# MCU_GPIO.net
KiCad netlist of a schematic drawn in Altium Designer
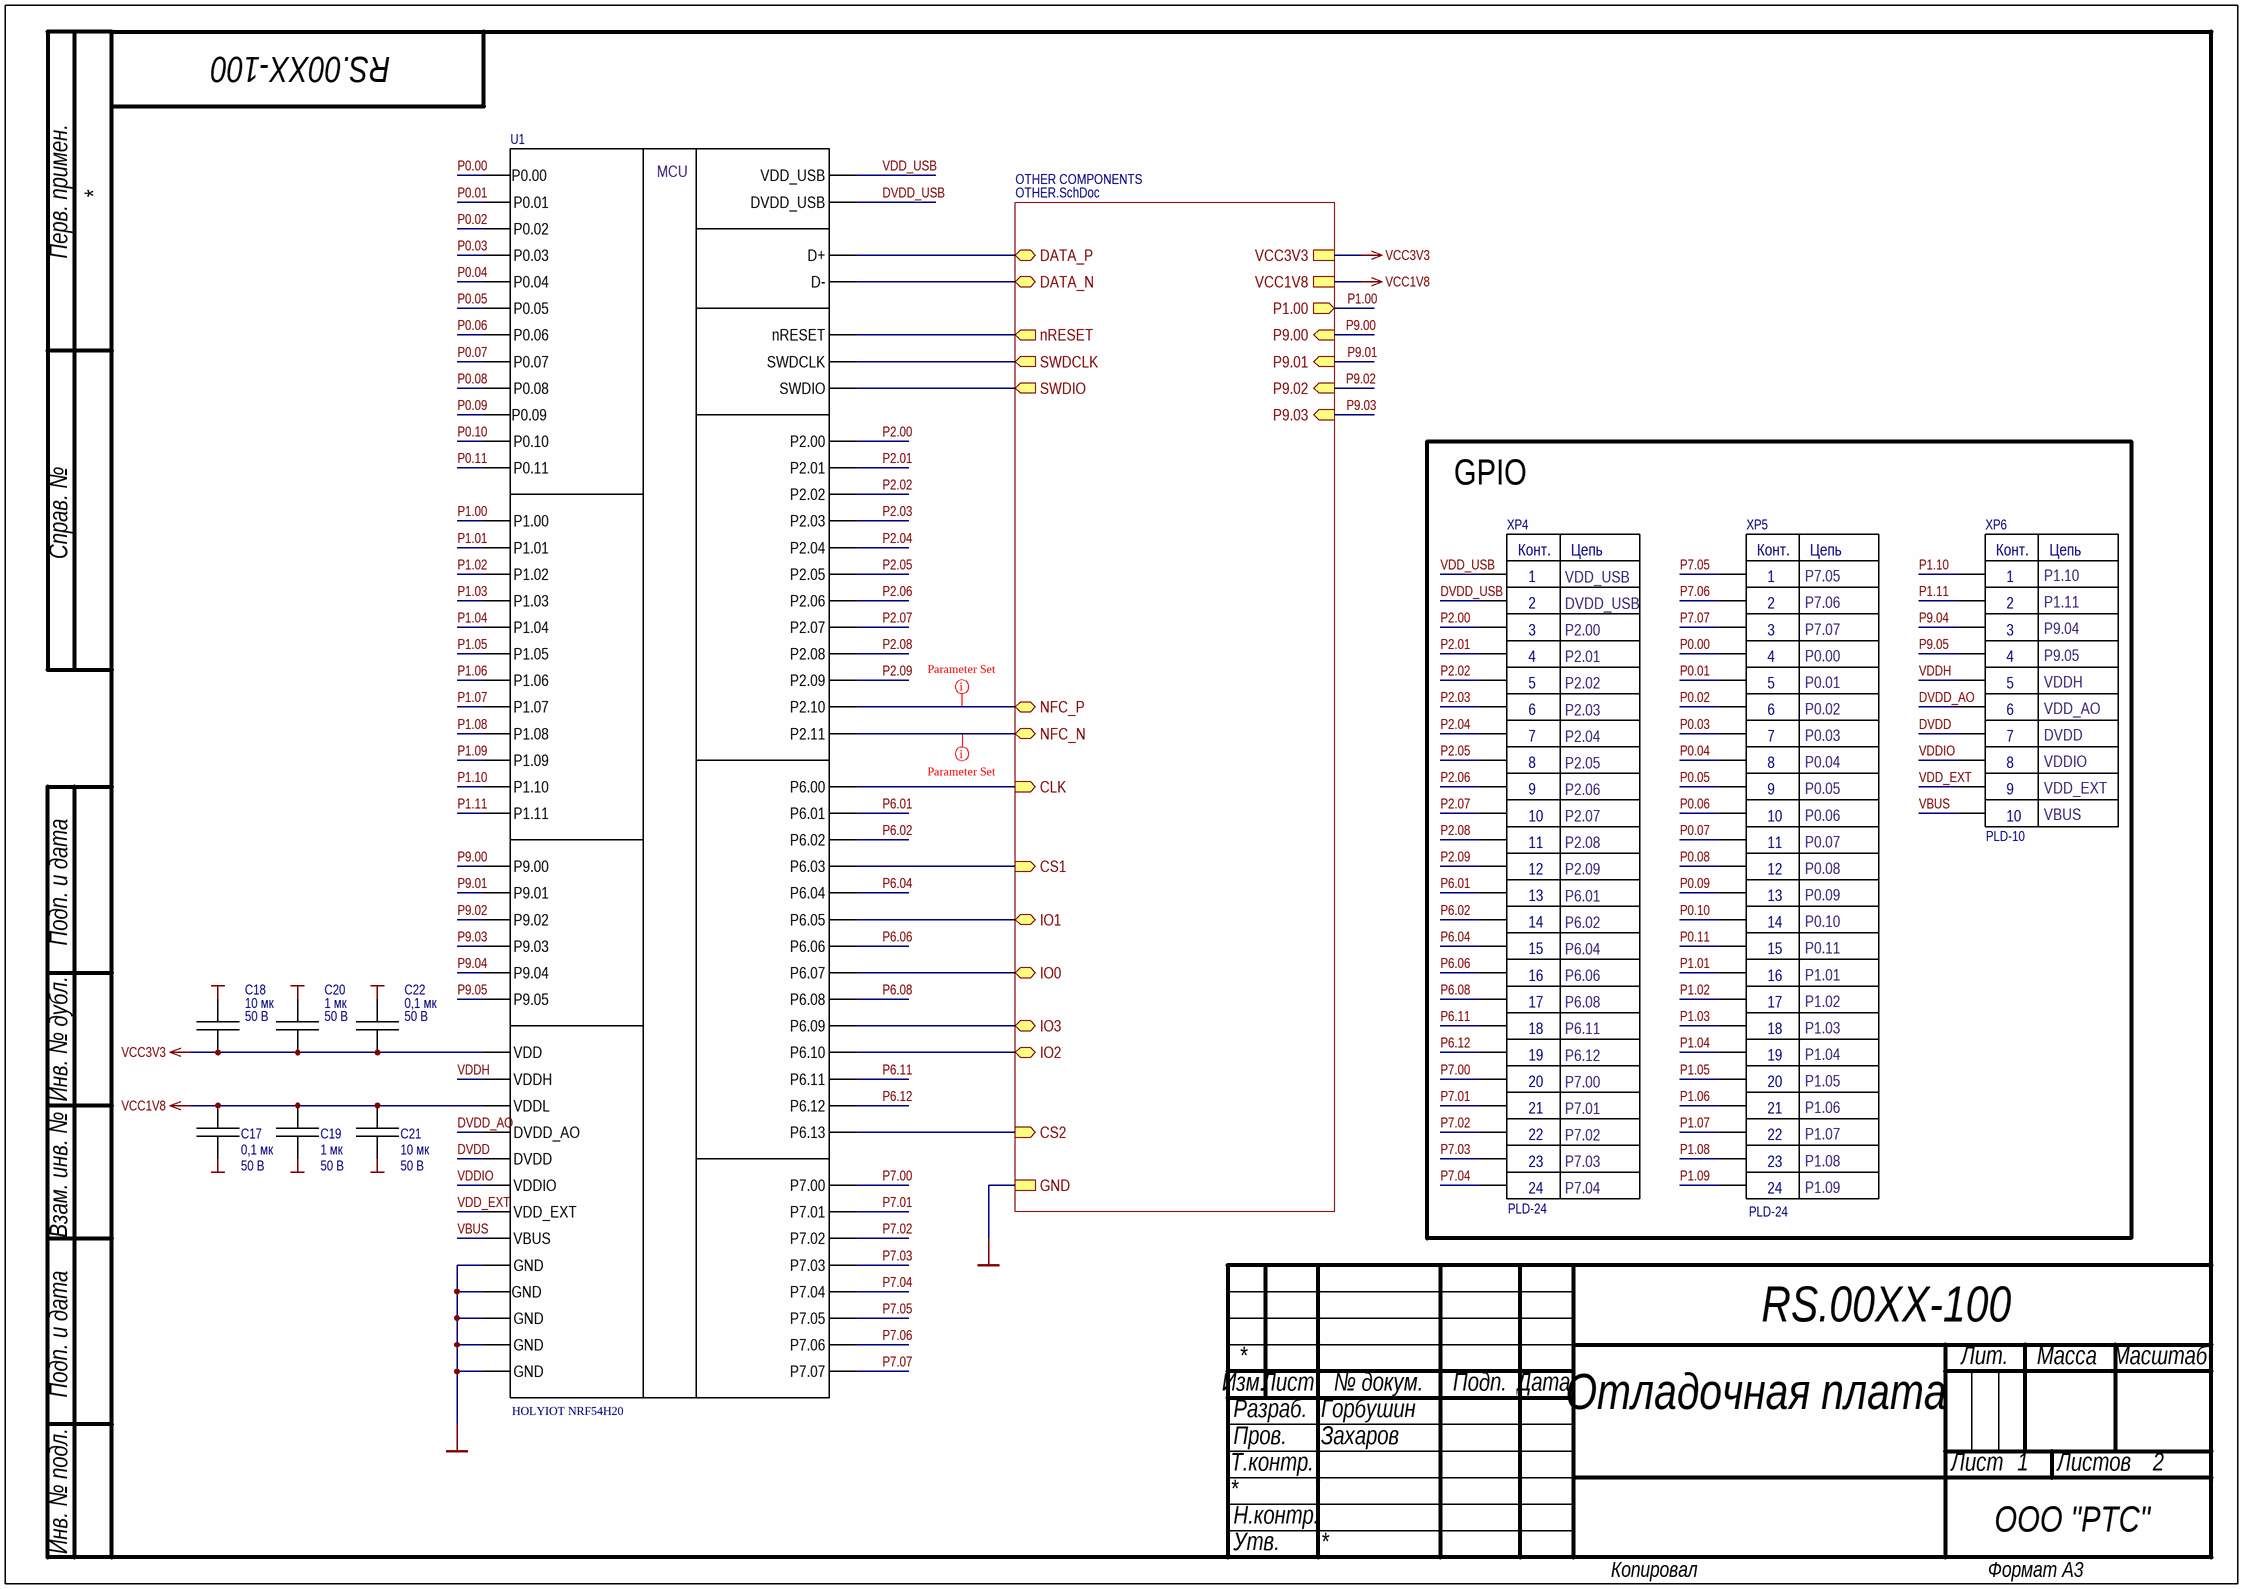
[diagram p0: MCU+GPIO.SchDoc]

(export (version "E")
  (design (tool "Eeschema 10.0.6"))
  (components
    (comp (ref "C17")
      (value "0,1 мк")
      (footprint "C_0603_Manual_mount")
      (description "Chip Monolithic Ceramic Capacitor")
      (fields
        (field (name "TOLERANCE") "10 %")
        (field (name "MANUFACTURER") "Murata Manufacturing")
        (field (name "RATED VOLTAGE") "50 В")
      )
      (libsource (lib "passive") (part "Capacitor"))
    )
    (comp (ref "C18")
      (value "10 мк")
      (footprint "C_1210_Manual_mount")
      (description "Chip Monolithic Ceramic Capacitor")
      (fields
        (field (name "TOLERANCE") "20 %")
        (field (name "MANUFACTURER") "Murata Manufacturing")
        (field (name "RATED VOLTAGE") "50 В")
      )
      (libsource (lib "passive") (part "Capacitor"))
    )
    (comp (ref "C19")
      (value "1 мк")
      (footprint "C_1206_Manual_mount")
      (description "Chip Monolithic Ceramic Capacitor")
      (fields
        (field (name "TOLERANCE") "10 %")
        (field (name "MANUFACTURER") "Murata Manufacturing")
        (field (name "RATED VOLTAGE") "50 В")
      )
      (libsource (lib "passive") (part "Capacitor"))
    )
    (comp (ref "C20")
      (value "1 мк")
      (footprint "C_1206_Manual_mount")
      (description "Chip Monolithic Ceramic Capacitor")
      (fields
        (field (name "TOLERANCE") "10 %")
        (field (name "MANUFACTURER") "Murata Manufacturing")
        (field (name "RATED VOLTAGE") "50 В")
      )
      (libsource (lib "passive") (part "Capacitor"))
    )
    (comp (ref "C21")
      (value "10 мк")
      (footprint "C_1210_Manual_mount")
      (description "Chip Monolithic Ceramic Capacitor")
      (fields
        (field (name "TOLERANCE") "20 %")
        (field (name "MANUFACTURER") "Murata Manufacturing")
        (field (name "RATED VOLTAGE") "50 В")
      )
      (libsource (lib "passive") (part "Capacitor"))
    )
    (comp (ref "C22")
      (value "0,1 мк")
      (footprint "C_0603_Manual_mount")
      (description "Chip Monolithic Ceramic Capacitor")
      (fields
        (field (name "TOLERANCE") "10 %")
        (field (name "MANUFACTURER") "Murata Manufacturing")
        (field (name "RATED VOLTAGE") "50 В")
      )
      (libsource (lib "passive") (part "Capacitor"))
    )
    (comp (ref "U1")
      (value "HOLYIOT NRF54H20")
      (footprint "HOLYIOT NRF54H20")
      (libsource (lib "Schlib1") (part "HOLYIOT NRF54H20"))
    )
    (comp (ref "XP4")
      (value "PLD-24")
      (footprint "PLD-24")
      (description "PLD connector")
      (fields (field (name "MANUFACTURER") "NONAME"))
      (libsource (lib "altium-lib") (part "PLD-24"))
    )
    (comp (ref "XP5")
      (value "PLD-24")
      (footprint "PLD-24")
      (description "PLD connector")
      (fields (field (name "MANUFACTURER") "NONAME"))
      (libsource (lib "altium-lib") (part "PLD-24"))
    )
    (comp (ref "XP6")
      (value "PLD-10")
      (footprint "PLD-10")
      (description "PLD connector")
      (fields (field (name "MANUFACTURER") "NONAME"))
      (libsource (lib "altium-lib") (part "PLD-10"))
    )
  )
  (nets
    (net (code "1") (name "/CLK") (class "Default")
      (node (ref "U1") (pin "15") (pinfunction "P6.00_15") (pintype "passive"))
    )
    (net (code "2") (name "/CS1") (class "Default")
      (node (ref "U1") (pin "18") (pinfunction "P6.03_18") (pintype "passive"))
    )
    (net (code "3") (name "/CS2") (class "Default")
      (node (ref "U1") (pin "7") (pinfunction "P6.13_7") (pintype "passive"))
    )
    (net (code "4") (name "/DATA_N") (class "Default")
      (node (ref "U1") (pin "78") (pinfunction "D-_78") (pintype "passive"))
    )
    (net (code "5") (name "/DATA_P") (class "Default")
      (node (ref "U1") (pin "79") (pinfunction "D+_79") (pintype "passive"))
    )
    (net (code "6") (name "/DVDD") (class "Default")
      (node (ref "U1") (pin "5") (pinfunction "DVDD_5") (pintype "passive"))
      (node (ref "XP6") (pin "7") (pinfunction "7_7") (pintype "passive"))
    )
    (net (code "7") (name "/DVDD_AO") (class "Default")
      (node (ref "U1") (pin "6") (pinfunction "DVDD_AO_6") (pintype "passive"))
      (node (ref "XP6") (pin "6") (pinfunction "6_6") (pintype "passive"))
    )
    (net (code "8") (name "/DVDD_USB") (class "Default")
      (node (ref "U1") (pin "76") (pinfunction "DVDD_USB_76") (pintype "passive"))
      (node (ref "XP4") (pin "2") (pinfunction "2_2") (pintype "passive"))
    )
    (net (code "9") (name "/IO0") (class "Default")
      (node (ref "U1") (pin "13") (pinfunction "P6.07_13") (pintype "passive"))
    )
    (net (code "10") (name "/IO1") (class "Default")
      (node (ref "U1") (pin "20") (pinfunction "P6.05_20") (pintype "passive"))
    )
    (net (code "11") (name "/IO2") (class "Default")
      (node (ref "U1") (pin "10") (pinfunction "P6.10_10") (pintype "passive"))
    )
    (net (code "12") (name "/IO3") (class "Default")
      (node (ref "U1") (pin "11") (pinfunction "P6.09_11") (pintype "passive"))
    )
    (net (code "13") (name "/NFC_N") (class "Default")
      (node (ref "U1") (pin "26") (pinfunction "P2.11_26") (pintype "passive"))
    )
    (net (code "14") (name "/NFC_P") (class "Default")
      (node (ref "U1") (pin "27") (pinfunction "P2.10_27") (pintype "passive"))
    )
    (net (code "15") (name "/P0.00") (class "Default")
      (node (ref "U1") (pin "50") (pinfunction "_P0.00_50") (pintype "passive"))
      (node (ref "XP5") (pin "4") (pinfunction "4_4") (pintype "passive"))
    )
    (net (code "16") (name "/P0.01") (class "Default")
      (node (ref "U1") (pin "68") (pinfunction "P0.01_68") (pintype "passive"))
      (node (ref "XP5") (pin "5") (pinfunction "5_5") (pintype "passive"))
    )
    (net (code "17") (name "/P0.02") (class "Default")
      (node (ref "U1") (pin "67") (pinfunction "P0.02_67") (pintype "passive"))
      (node (ref "XP5") (pin "6") (pinfunction "6_6") (pintype "passive"))
    )
    (net (code "18") (name "/P0.03") (class "Default")
      (node (ref "U1") (pin "66") (pinfunction "P0.03_66") (pintype "passive"))
      (node (ref "XP5") (pin "7") (pinfunction "7_7") (pintype "passive"))
    )
    (net (code "19") (name "/P0.04") (class "Default")
      (node (ref "U1") (pin "51") (pinfunction "P0.04_51") (pintype "passive"))
      (node (ref "XP5") (pin "8") (pinfunction "8_8") (pintype "passive"))
    )
    (net (code "20") (name "/P0.05") (class "Default")
      (node (ref "U1") (pin "45") (pinfunction "P0.05_45") (pintype "passive"))
      (node (ref "XP5") (pin "9") (pinfunction "9_9") (pintype "passive"))
    )
    (net (code "21") (name "/P0.06") (class "Default")
      (node (ref "U1") (pin "46") (pinfunction "P0.06_46") (pintype "passive"))
      (node (ref "XP5") (pin "10") (pinfunction "10_10") (pintype "passive"))
    )
    (net (code "22") (name "/P0.07") (class "Default")
      (node (ref "U1") (pin "47") (pinfunction "P0.07_47") (pintype "passive"))
      (node (ref "XP5") (pin "11") (pinfunction "11_11") (pintype "passive"))
    )
    (net (code "23") (name "/P0.08") (class "Default")
      (node (ref "U1") (pin "44") (pinfunction "P0.08_44") (pintype "passive"))
      (node (ref "XP5") (pin "12") (pinfunction "12_12") (pintype "passive"))
    )
    (net (code "24") (name "/P0.09") (class "Default")
      (node (ref "U1") (pin "43") (pinfunction "_P0.09_43") (pintype "passive"))
      (node (ref "XP5") (pin "13") (pinfunction "13_13") (pintype "passive"))
    )
    (net (code "25") (name "/P0.10") (class "Default")
      (node (ref "U1") (pin "69") (pinfunction "P0.10_69") (pintype "passive"))
      (node (ref "XP5") (pin "14") (pinfunction "14_14") (pintype "passive"))
    )
    (net (code "26") (name "/P0.11") (class "Default")
      (node (ref "U1") (pin "70") (pinfunction "P0.11_70") (pintype "passive"))
      (node (ref "XP5") (pin "15") (pinfunction "15_15") (pintype "passive"))
    )
    (net (code "27") (name "/P1.00") (class "Default")
      (node (ref "U1") (pin "57") (pinfunction "P1.00_57") (pintype "passive"))
    )
    (net (code "28") (name "/P1.01") (class "Default")
      (node (ref "U1") (pin "56") (pinfunction "P1.01_56") (pintype "passive"))
      (node (ref "XP5") (pin "16") (pinfunction "16_16") (pintype "passive"))
    )
    (net (code "29") (name "/P1.02") (class "Default")
      (node (ref "U1") (pin "54") (pinfunction "P1.02_54") (pintype "passive"))
      (node (ref "XP5") (pin "17") (pinfunction "17_17") (pintype "passive"))
    )
    (net (code "30") (name "/P1.03") (class "Default")
      (node (ref "U1") (pin "53") (pinfunction "P1.03_53") (pintype "passive"))
      (node (ref "XP5") (pin "18") (pinfunction "18_18") (pintype "passive"))
    )
    (net (code "31") (name "/P1.04") (class "Default")
      (node (ref "U1") (pin "52") (pinfunction "P1.04_52") (pintype "passive"))
      (node (ref "XP5") (pin "19") (pinfunction "19_19") (pintype "passive"))
    )
    (net (code "32") (name "/P1.05") (class "Default")
      (node (ref "U1") (pin "84") (pinfunction "P1.05_84") (pintype "passive"))
      (node (ref "XP5") (pin "20") (pinfunction "20_20") (pintype "passive"))
    )
    (net (code "33") (name "/P1.06") (class "Default")
      (node (ref "U1") (pin "59") (pinfunction "P1.06_59") (pintype "passive"))
      (node (ref "XP5") (pin "21") (pinfunction "21_21") (pintype "passive"))
    )
    (net (code "34") (name "/P1.07") (class "Default")
      (node (ref "U1") (pin "60") (pinfunction "P1.07_60") (pintype "passive"))
      (node (ref "XP5") (pin "22") (pinfunction "22_22") (pintype "passive"))
    )
    (net (code "35") (name "/P1.08") (class "Default")
      (node (ref "U1") (pin "83") (pinfunction "P1.08_83") (pintype "passive"))
      (node (ref "XP5") (pin "23") (pinfunction "23_23") (pintype "passive"))
    )
    (net (code "36") (name "/P1.09") (class "Default")
      (node (ref "U1") (pin "61") (pinfunction "P1.09_61") (pintype "passive"))
      (node (ref "XP5") (pin "24") (pinfunction "24_24") (pintype "passive"))
    )
    (net (code "37") (name "/P1.10") (class "Default")
      (node (ref "U1") (pin "81") (pinfunction "P1.10_81") (pintype "passive"))
      (node (ref "XP6") (pin "1") (pinfunction "1_1") (pintype "passive"))
    )
    (net (code "38") (name "/P1.11") (class "Default")
      (node (ref "U1") (pin "82") (pinfunction "P1.11_82") (pintype "passive"))
      (node (ref "XP6") (pin "2") (pinfunction "2_2") (pintype "passive"))
    )
    (net (code "39") (name "/P2.00") (class "Default")
      (node (ref "U1") (pin "21") (pinfunction "P2.00_21") (pintype "passive"))
      (node (ref "XP4") (pin "3") (pinfunction "3_3") (pintype "passive"))
    )
    (net (code "40") (name "/P2.01") (class "Default")
      (node (ref "U1") (pin "22") (pinfunction "P2.01_22") (pintype "passive"))
      (node (ref "XP4") (pin "4") (pinfunction "4_4") (pintype "passive"))
    )
    (net (code "41") (name "/P2.02") (class "Default")
      (node (ref "U1") (pin "23") (pinfunction "P2.02_23") (pintype "passive"))
      (node (ref "XP4") (pin "5") (pinfunction "5_5") (pintype "passive"))
    )
    (net (code "42") (name "/P2.03") (class "Default")
      (node (ref "U1") (pin "24") (pinfunction "P2.03_24") (pintype "passive"))
      (node (ref "XP4") (pin "6") (pinfunction "6_6") (pintype "passive"))
    )
    (net (code "43") (name "/P2.04") (class "Default")
      (node (ref "U1") (pin "25") (pinfunction "P2.04_25") (pintype "passive"))
      (node (ref "XP4") (pin "7") (pinfunction "7_7") (pintype "passive"))
    )
    (net (code "44") (name "/P2.05") (class "Default")
      (node (ref "U1") (pin "34") (pinfunction "P2.05_34") (pintype "passive"))
      (node (ref "XP4") (pin "8") (pinfunction "8_8") (pintype "passive"))
    )
    (net (code "45") (name "/P2.06") (class "Default")
      (node (ref "U1") (pin "33") (pinfunction "P2.06_33") (pintype "passive"))
      (node (ref "XP4") (pin "9") (pinfunction "9_9") (pintype "passive"))
    )
    (net (code "46") (name "/P2.07") (class "Default")
      (node (ref "U1") (pin "32") (pinfunction "P2.07_32") (pintype "passive"))
      (node (ref "XP4") (pin "10") (pinfunction "10_10") (pintype "passive"))
    )
    (net (code "47") (name "/P2.08") (class "Default")
      (node (ref "U1") (pin "31") (pinfunction "P2.08_31") (pintype "passive"))
      (node (ref "XP4") (pin "11") (pinfunction "11_11") (pintype "passive"))
    )
    (net (code "48") (name "/P2.09") (class "Default")
      (node (ref "U1") (pin "30") (pinfunction "P2.09_30") (pintype "passive"))
      (node (ref "XP4") (pin "12") (pinfunction "12_12") (pintype "passive"))
    )
    (net (code "49") (name "/P6.01") (class "Default")
      (node (ref "U1") (pin "16") (pinfunction "P6.01_16") (pintype "passive"))
      (node (ref "XP4") (pin "13") (pinfunction "13_13") (pintype "passive"))
    )
    (net (code "50") (name "/P6.02") (class "Default")
      (node (ref "U1") (pin "17") (pinfunction "P6.02_17") (pintype "passive"))
      (node (ref "XP4") (pin "14") (pinfunction "14_14") (pintype "passive"))
    )
    (net (code "51") (name "/P6.04") (class "Default")
      (node (ref "U1") (pin "19") (pinfunction "P6.04_19") (pintype "passive"))
      (node (ref "XP4") (pin "15") (pinfunction "15_15") (pintype "passive"))
    )
    (net (code "52") (name "/P6.06") (class "Default")
      (node (ref "U1") (pin "14") (pinfunction "P6.06_14") (pintype "passive"))
      (node (ref "XP4") (pin "16") (pinfunction "16_16") (pintype "passive"))
    )
    (net (code "53") (name "/P6.08") (class "Default")
      (node (ref "U1") (pin "12") (pinfunction "P6.08_12") (pintype "passive"))
      (node (ref "XP4") (pin "17") (pinfunction "17_17") (pintype "passive"))
    )
    (net (code "54") (name "/P6.11") (class "Default")
      (node (ref "U1") (pin "9") (pinfunction "P6.11_9") (pintype "passive"))
      (node (ref "XP4") (pin "18") (pinfunction "18_18") (pintype "passive"))
    )
    (net (code "55") (name "/P6.12") (class "Default")
      (node (ref "U1") (pin "8") (pinfunction "P6.12_8") (pintype "passive"))
      (node (ref "XP4") (pin "19") (pinfunction "19_19") (pintype "passive"))
    )
    (net (code "56") (name "/P7.00") (class "Default")
      (node (ref "U1") (pin "42") (pinfunction "P7.00_42") (pintype "passive"))
      (node (ref "XP4") (pin "20") (pinfunction "20_20") (pintype "passive"))
    )
    (net (code "57") (name "/P7.01") (class "Default")
      (node (ref "U1") (pin "41") (pinfunction "P7.01_41") (pintype "passive"))
      (node (ref "XP4") (pin "21") (pinfunction "21_21") (pintype "passive"))
    )
    (net (code "58") (name "/P7.02") (class "Default")
      (node (ref "U1") (pin "40") (pinfunction "P7.02_40") (pintype "passive"))
      (node (ref "XP4") (pin "22") (pinfunction "22_22") (pintype "passive"))
    )
    (net (code "59") (name "/P7.03") (class "Default")
      (node (ref "U1") (pin "39") (pinfunction "P7.03_39") (pintype "passive"))
      (node (ref "XP4") (pin "23") (pinfunction "23_23") (pintype "passive"))
    )
    (net (code "60") (name "/P7.04") (class "Default")
      (node (ref "U1") (pin "38") (pinfunction "P7.04_38") (pintype "passive"))
      (node (ref "XP4") (pin "24") (pinfunction "24_24") (pintype "passive"))
    )
    (net (code "61") (name "/P7.05") (class "Default")
      (node (ref "U1") (pin "37") (pinfunction "P7.05_37") (pintype "passive"))
      (node (ref "XP5") (pin "1") (pinfunction "1_1") (pintype "passive"))
    )
    (net (code "62") (name "/P7.06") (class "Default")
      (node (ref "U1") (pin "36") (pinfunction "P7.06_36") (pintype "passive"))
      (node (ref "XP5") (pin "2") (pinfunction "2_2") (pintype "passive"))
    )
    (net (code "63") (name "/P7.07") (class "Default")
      (node (ref "U1") (pin "35") (pinfunction "P7.07_35") (pintype "passive"))
      (node (ref "XP5") (pin "3") (pinfunction "3_3") (pintype "passive"))
    )
    (net (code "64") (name "/P9.00") (class "Default")
      (node (ref "U1") (pin "48") (pinfunction "P9.00_48") (pintype "passive"))
    )
    (net (code "65") (name "/P9.01") (class "Default")
      (node (ref "U1") (pin "49") (pinfunction "P9.01_49") (pintype "passive"))
    )
    (net (code "66") (name "/P9.02") (class "Default")
      (node (ref "U1") (pin "65") (pinfunction "P9.02_65") (pintype "passive"))
    )
    (net (code "67") (name "/P9.03") (class "Default")
      (node (ref "U1") (pin "64") (pinfunction "P9.03_64") (pintype "passive"))
    )
    (net (code "68") (name "/P9.04") (class "Default")
      (node (ref "U1") (pin "63") (pinfunction "P9.04_63") (pintype "passive"))
      (node (ref "XP6") (pin "3") (pinfunction "3_3") (pintype "passive"))
    )
    (net (code "69") (name "/P9.05") (class "Default")
      (node (ref "U1") (pin "62") (pinfunction "P9.05_62") (pintype "passive"))
      (node (ref "XP6") (pin "4") (pinfunction "4_4") (pintype "passive"))
    )
    (net (code "70") (name "/SWDCLK") (class "Default")
      (node (ref "U1") (pin "74") (pinfunction "SWDCLK_74") (pintype "passive"))
    )
    (net (code "71") (name "/SWDIO") (class "Default")
      (node (ref "U1") (pin "73") (pinfunction "SWDIO_73") (pintype "passive"))
    )
    (net (code "72") (name "/VBUS") (class "Default")
      (node (ref "U1") (pin "77") (pinfunction "VBUS_77") (pintype "passive"))
      (node (ref "XP6") (pin "10") (pinfunction "10_10") (pintype "passive"))
    )
    (net (code "73") (name "/VDDH") (class "Default")
      (node (ref "U1") (pin "2") (pinfunction "VDDH_2") (pintype "passive"))
      (node (ref "XP6") (pin "5") (pinfunction "5_5") (pintype "passive"))
    )
    (net (code "74") (name "/VDDIO") (class "Default")
      (node (ref "U1") (pin "71") (pinfunction "VDDIO_71") (pintype "passive"))
      (node (ref "XP6") (pin "8") (pinfunction "8_8") (pintype "passive"))
    )
    (net (code "75") (name "/VDD_EXT") (class "Default")
      (node (ref "U1") (pin "75") (pinfunction "VDD_EXT_75") (pintype "passive"))
      (node (ref "XP6") (pin "9") (pinfunction "9_9") (pintype "passive"))
    )
    (net (code "76") (name "/VDD_USB") (class "Default")
      (node (ref "U1") (pin "80") (pinfunction "VDD_USB_80") (pintype "passive"))
      (node (ref "XP4") (pin "1") (pinfunction "1_1") (pintype "passive"))
    )
    (net (code "77") (name "/nRESET") (class "Default")
      (node (ref "U1") (pin "72") (pinfunction "nRESET_72") (pintype "passive"))
    )
    (net (code "78") (name "GND") (class "Default")
      (node (ref "C17") (pin "2") (pinfunction "2_2") (pintype "passive"))
      (node (ref "C18") (pin "2") (pinfunction "2_2") (pintype "passive"))
      (node (ref "C19") (pin "2") (pinfunction "2_2") (pintype "passive"))
      (node (ref "C20") (pin "2") (pinfunction "2_2") (pintype "passive"))
      (node (ref "C21") (pin "2") (pinfunction "2_2") (pintype "passive"))
      (node (ref "C22") (pin "2") (pinfunction "2_2") (pintype "passive"))
      (node (ref "U1") (pin "1") (pinfunction "GND_1") (pintype "passive"))
      (node (ref "U1") (pin "28") (pinfunction "GND_28") (pintype "passive"))
      (node (ref "U1") (pin "29") (pinfunction "GND_29") (pintype "passive"))
      (node (ref "U1") (pin "4") (pinfunction "_GND_4") (pintype "passive"))
      (node (ref "U1") (pin "58") (pinfunction "GND_58") (pintype "passive"))
    )
    (net (code "79") (name "VCC1V8") (class "Default")
      (node (ref "C17") (pin "1") (pinfunction "1_1") (pintype "passive"))
      (node (ref "C19") (pin "1") (pinfunction "1_1") (pintype "passive"))
      (node (ref "C21") (pin "1") (pinfunction "1_1") (pintype "passive"))
      (node (ref "U1") (pin "55") (pinfunction "VDDL_55") (pintype "passive"))
    )
    (net (code "80") (name "VCC3V3") (class "Default")
      (node (ref "C18") (pin "1") (pinfunction "1_1") (pintype "passive"))
      (node (ref "C20") (pin "1") (pinfunction "1_1") (pintype "passive"))
      (node (ref "C22") (pin "1") (pinfunction "1_1") (pintype "passive"))
      (node (ref "U1") (pin "3") (pinfunction "VDD_3") (pintype "passive"))
    )
  )
)
